# XJTLU_Torpedo.net
KiCad netlist of a schematic drawn in Altium Designer
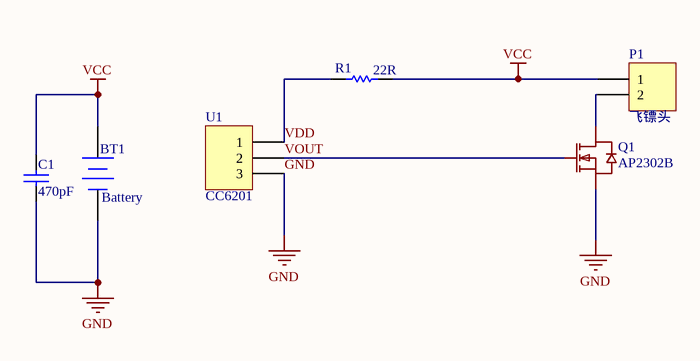
[diagram p0: XJTLU_Torpedo.SchDoc]

(export (version "E")
  (design (tool "Eeschema 10.0.6"))
  (components
    (comp (ref "BT1")
      (value "Battery")
      (footprint "BAT-2")
      (description "Multicell Battery")
      (fields (field (name "PUBLISHER") "Altium Limited"))
      (libsource (lib "Miscellaneous Devices") (part "Battery"))
    )
    (comp (ref "C1")
      (value "470pF")
      (footprint "C0603")
      (description "Capacitor")
      (fields (field (name "Comment") "Cap") (field (name "PUBLISHER") "Altium Limited"))
      (libsource (lib "Miscellaneous Devices") (part "Cap"))
    )
    (comp (ref "P1")
      (value "飞镖头")
      (footprint "BAT-2")
      (description "Header, 2-Pin")
      (fields (field (name "PUBLISHER") "Altium Limited"))
      (libsource (lib "Miscellaneous Connectors") (part "Header 2"))
    )
    (comp (ref "Q1")
      (value "AP2302B")
      (footprint "SOT-23-3")
      (description "20V N-Channel Enhancement Mode MOSFET")
      (libsource (lib "XJTLU_Torpedo") (part "AP2302BI"))
    )
    (comp (ref "R1")
      (value "22R")
      (footprint "R0603")
      (description "Resistor")
      (fields (field (name "Comment") "Res1") (field (name "PUBLISHER") "Altium Limited"))
      (libsource (lib "Miscellaneous Devices") (part "Res1"))
    )
    (comp (ref "U1")
      (value "CC6201")
      (footprint "TSOT-23-3")
      (description "Header, 3-Pin")
      (fields (field (name "PUBLISHER") "Altium Limited"))
      (libsource (lib "Miscellaneous Connectors") (part "Header 3"))
    )
  )
  (nets
    (net (code "1") (name "/VDD") (class "Default")
      (node (ref "R1") (pin "2") (pinfunction "2_2") (pintype "passive"))
      (node (ref "U1") (pin "1") (pinfunction "1_1") (pintype "passive"))
    )
    (net (code "2") (name "/VOUT") (class "Default")
      (node (ref "Q1") (pin "1") (pinfunction "G_1") (pintype "passive"))
      (node (ref "U1") (pin "2") (pinfunction "2_2") (pintype "passive"))
    )
    (net (code "3") (name "GND") (class "Default")
      (node (ref "BT1") (pin "2") (pinfunction "-_2") (pintype "passive"))
      (node (ref "C1") (pin "1") (pinfunction "1_1") (pintype "passive"))
      (node (ref "Q1") (pin "2") (pinfunction "S_2") (pintype "passive"))
      (node (ref "U1") (pin "3") (pinfunction "3_3") (pintype "passive"))
    )
    (net (code "4") (name "Net-(Q1-D)") (class "Default")
      (node (ref "P1") (pin "2") (pinfunction "2_2") (pintype "passive"))
      (node (ref "Q1") (pin "3") (pinfunction "D_3") (pintype "passive"))
    )
    (net (code "5") (name "VCC") (class "Default")
      (node (ref "BT1") (pin "1") (pinfunction "+_1") (pintype "passive"))
      (node (ref "C1") (pin "2") (pinfunction "2_2") (pintype "passive"))
      (node (ref "P1") (pin "1") (pinfunction "1_1") (pintype "passive"))
      (node (ref "R1") (pin "1") (pinfunction "1_1") (pintype "passive"))
    )
  )
)
